# Nixius.net
KiCad netlist of a schematic drawn in EAGLE
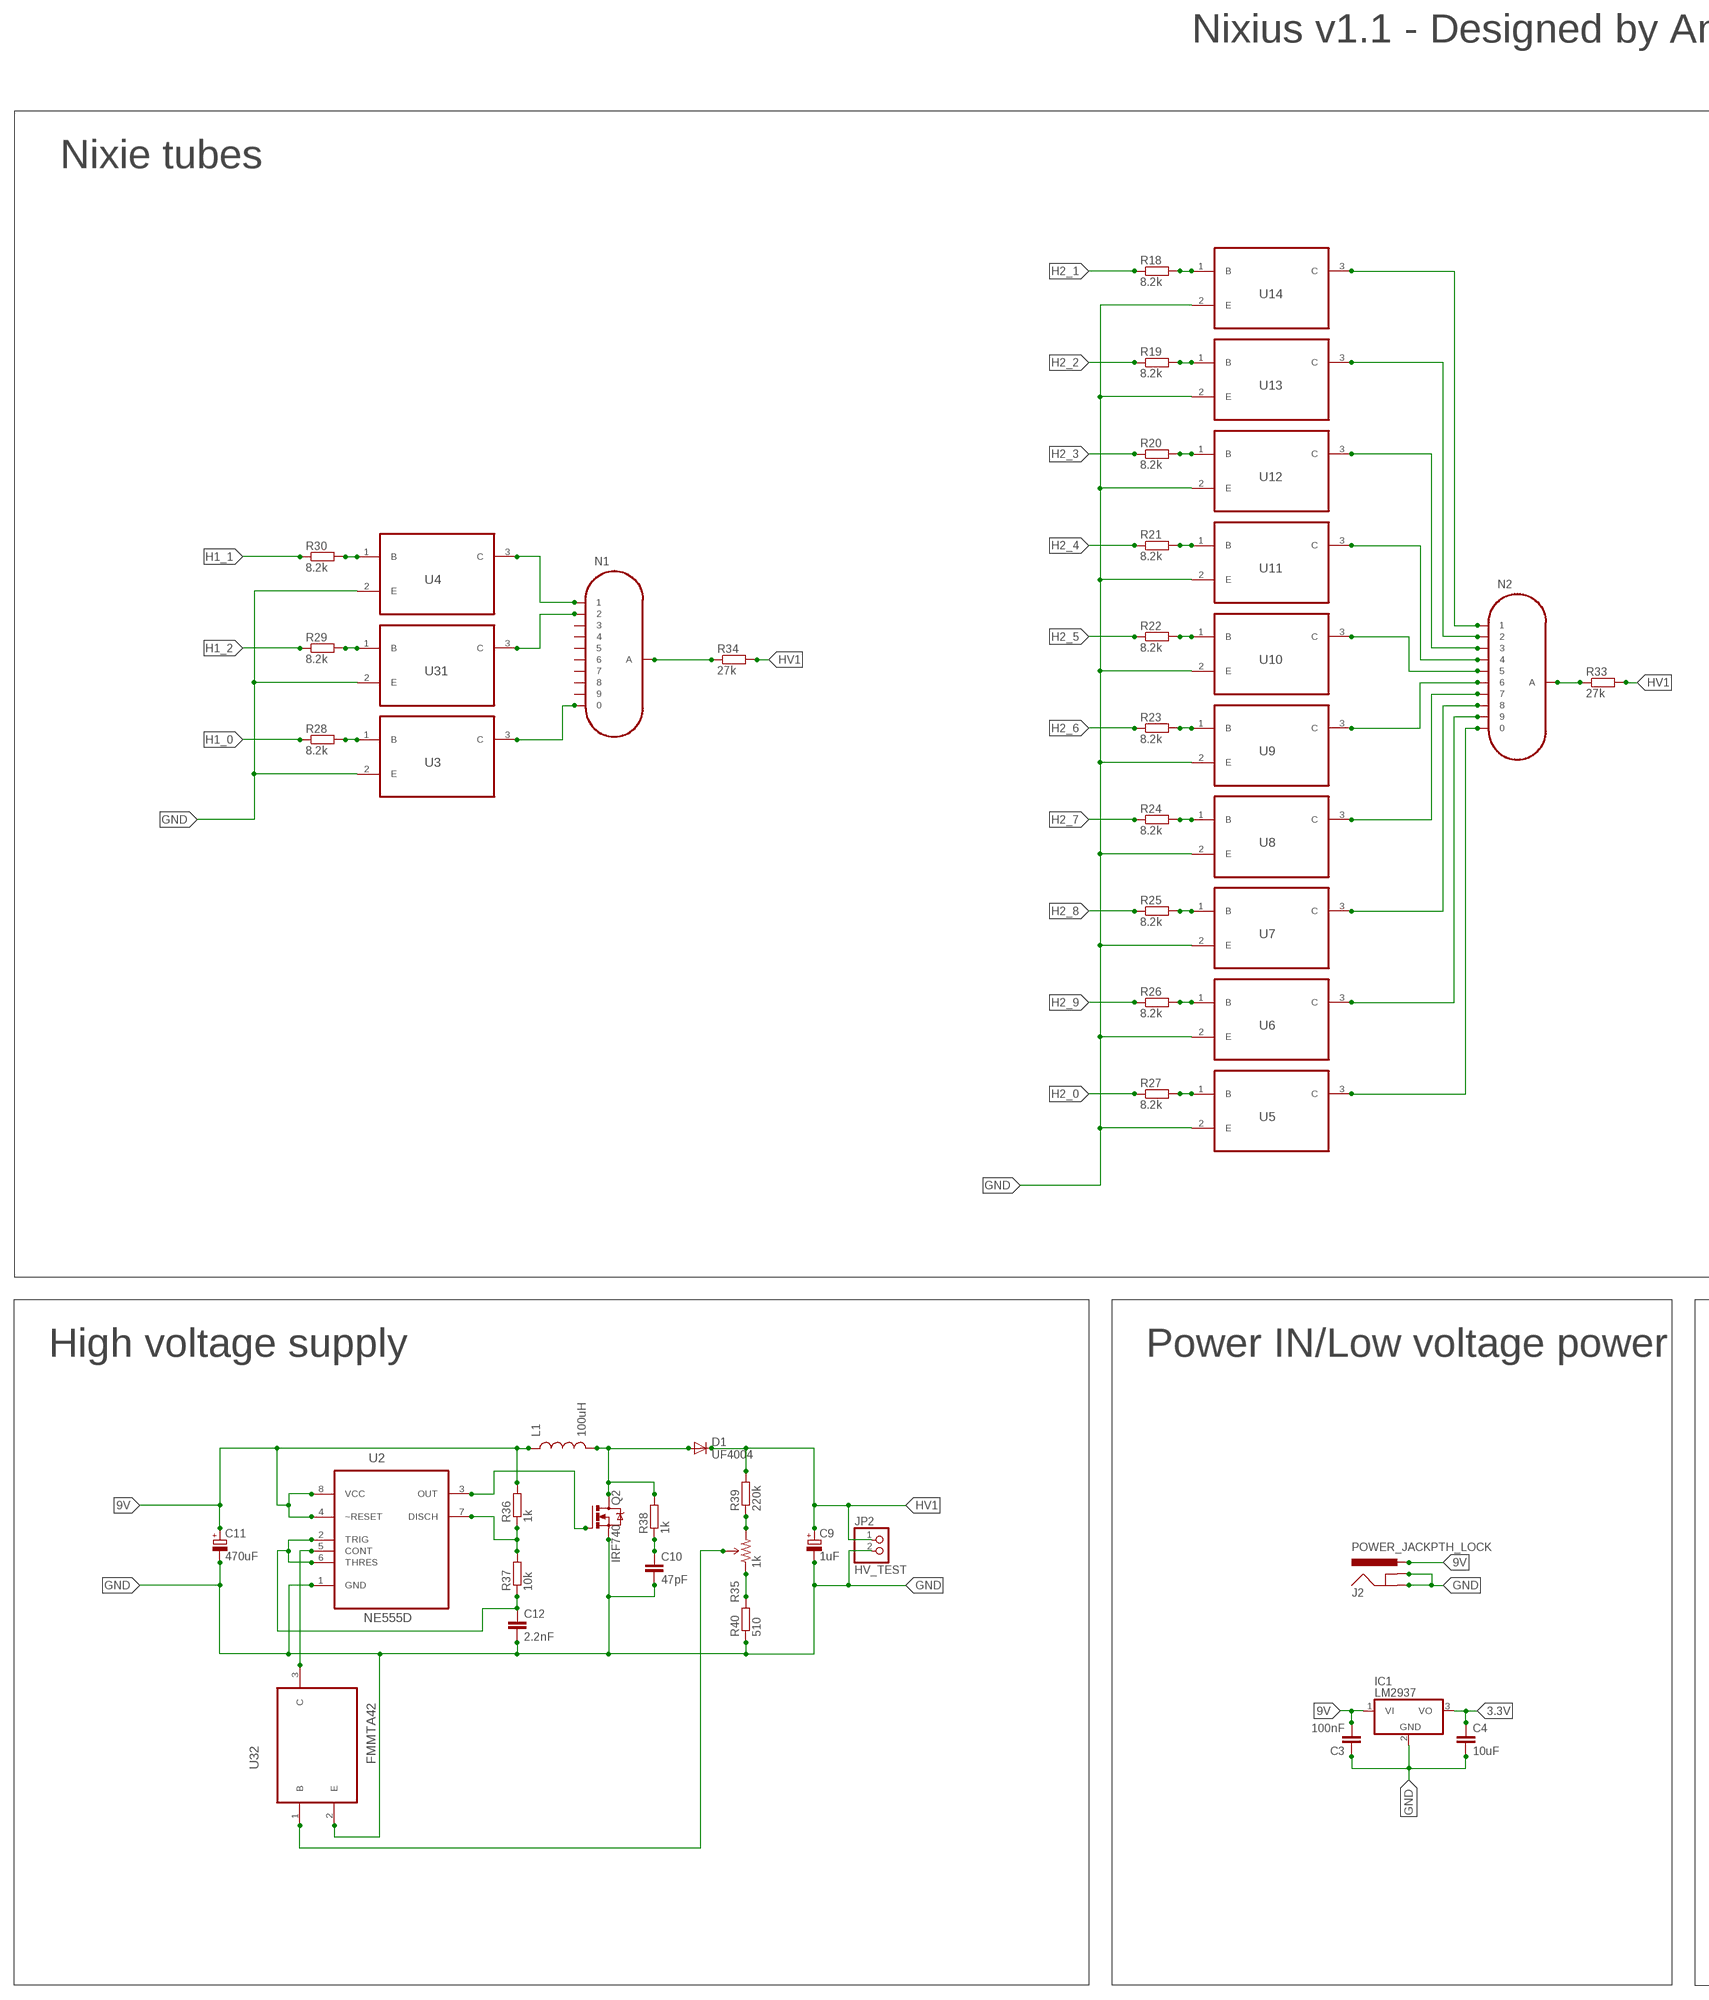
[diagram p0: schematic, sheet 1, part 1 of 2]
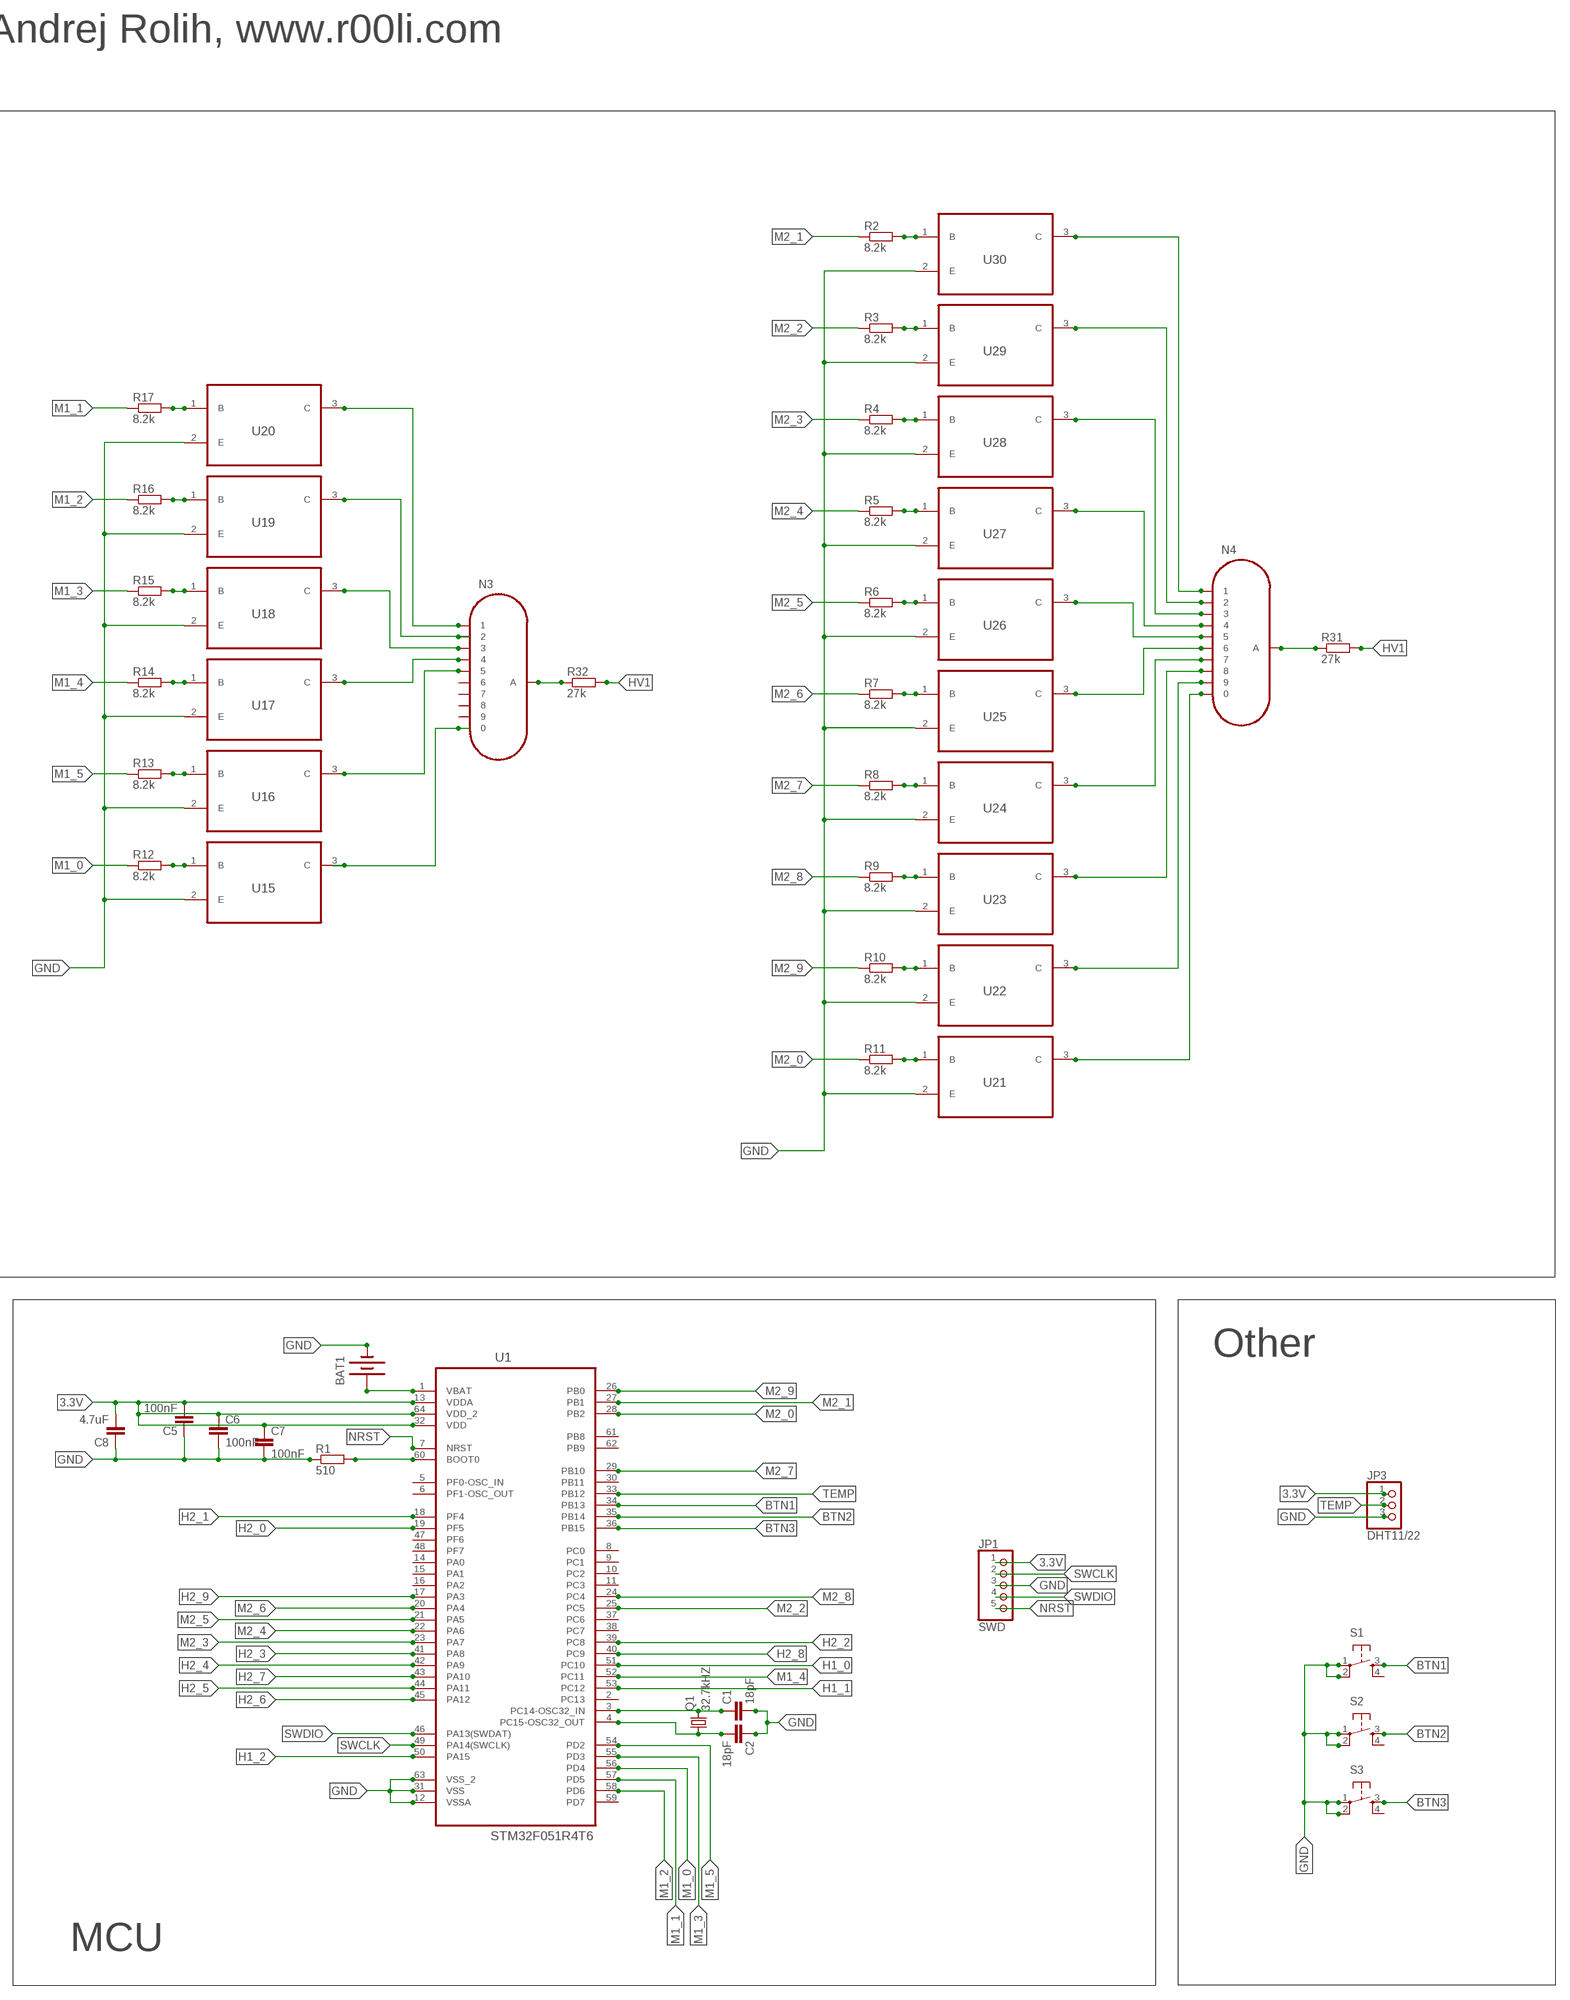
[diagram p1: schematic, sheet 1, part 2 of 2]

(export (version "E")
  (design (tool "Eeschema 10.0.6"))
  (components
    (comp (ref "BAT1")
      (value "BATTERY20SMD")
      (footprint "eagle-import:BATTCON_20MM")
      (libsource (lib "eagle-import") (part "BATTERY20SMD"))
    )
    (comp (ref "C1")
      (value "18pF")
      (footprint "eagle-import:0805")
      (libsource (lib "eagle-import") (part "CAP0805"))
    )
    (comp (ref "C2")
      (value "18pF")
      (footprint "eagle-import:0805")
      (libsource (lib "eagle-import") (part "CAP0805"))
    )
    (comp (ref "C3")
      (value "100nF")
      (footprint "eagle-import:0805")
      (libsource (lib "eagle-import") (part "CAP0805"))
    )
    (comp (ref "C4")
      (value "10uF")
      (footprint "eagle-import:0805")
      (libsource (lib "eagle-import") (part "CAP0805"))
    )
    (comp (ref "C5")
      (value "100nF")
      (footprint "eagle-import:0805")
      (libsource (lib "eagle-import") (part "CAP0805"))
    )
    (comp (ref "C6")
      (value "100nF")
      (footprint "eagle-import:0805")
      (libsource (lib "eagle-import") (part "CAP0805"))
    )
    (comp (ref "C7")
      (value "100nF")
      (footprint "eagle-import:0805")
      (libsource (lib "eagle-import") (part "CAP0805"))
    )
    (comp (ref "C8")
      (value "4.7uF")
      (footprint "eagle-import:0805")
      (libsource (lib "eagle-import") (part "CAP0805"))
    )
    (comp (ref "C9")
      (value "1uF")
      (footprint "eagle-import:E2,5-6")
      (libsource (lib "eagle-import") (part "CPOL-EUE2.5-6"))
    )
    (comp (ref "C10")
      (value "47pF")
      (footprint "eagle-import:0805")
      (libsource (lib "eagle-import") (part "CAP0805"))
    )
    (comp (ref "C11")
      (value "470uF")
      (footprint "eagle-import:E3,5-8")
      (libsource (lib "eagle-import") (part "CPOL-EUE3.5-8"))
    )
    (comp (ref "C12")
      (value "2.2nF")
      (footprint "eagle-import:C050-025X075")
      (libsource (lib "eagle-import") (part "C-EU050-025X075"))
    )
    (comp (ref "D1")
      (value "UF4004")
      (footprint "eagle-import:DO41-10")
      (libsource (lib "eagle-import") (part "1N4004"))
    )
    (comp (ref "IC1")
      (value "LM2937")
      (footprint "eagle-import:TO263-3")
      (libsource (lib "eagle-import") (part "LM2937"))
    )
    (comp (ref "J2")
      (value "POWER_JACKPTH_LOCK")
      (footprint "eagle-import:POWER_JACK_PTH_LOCK")
      (libsource (lib "eagle-import") (part "POWER_JACKPTH_LOCK"))
    )
    (comp (ref "JP1")
      (value "SWD")
      (footprint "eagle-import:1X05")
      (libsource (lib "eagle-import") (part "PINHD-1X5"))
    )
    (comp (ref "JP2")
      (value "HV_TEST")
      (footprint "eagle-import:1X02")
      (libsource (lib "eagle-import") (part "PINHD-1X2"))
    )
    (comp (ref "JP3")
      (value "DHT11/22")
      (footprint "eagle-import:1X03")
      (libsource (lib "eagle-import") (part "PINHD-1X3"))
    )
    (comp (ref "L1")
      (value "100uH")
      (footprint "eagle-import:RLB0912")
      (libsource (lib "eagle-import") (part "INDUCTORRLB0912"))
    )
    (comp (ref "N1")
      (value "IN-1")
      (footprint "eagle-import:IN-1")
      (libsource (lib "eagle-import") (part "IN-1"))
    )
    (comp (ref "N2")
      (value "IN-1")
      (footprint "eagle-import:IN-1")
      (libsource (lib "eagle-import") (part "IN-1"))
    )
    (comp (ref "N3")
      (value "IN-1")
      (footprint "eagle-import:IN-1")
      (libsource (lib "eagle-import") (part "IN-1"))
    )
    (comp (ref "N4")
      (value "IN-1")
      (footprint "eagle-import:IN-1")
      (libsource (lib "eagle-import") (part "IN-1"))
    )
    (comp (ref "Q1")
      (value "32.7kHZ")
      (footprint "eagle-import:MC-306")
      (fields (field (name "MPN") "MC-306 60.0KHZ  100PPM ,12.5PF"))
      (libsource (lib "eagle-import") (part "MC-306"))
    )
    (comp (ref "Q2")
      (value "IRF740")
      (footprint "eagle-import:TO220BV")
      (libsource (lib "eagle-import") (part "IRF740"))
    )
    (comp (ref "R1")
      (value "510")
      (footprint "eagle-import:R0805")
      (libsource (lib "eagle-import") (part "resistor_R-EU_R0805"))
    )
    (comp (ref "R2")
      (value "8.2k")
      (footprint "eagle-import:R0805")
      (libsource (lib "eagle-import") (part "resistor_R-EU_R0805"))
    )
    (comp (ref "R3")
      (value "8.2k")
      (footprint "eagle-import:R0805")
      (libsource (lib "eagle-import") (part "resistor_R-EU_R0805"))
    )
    (comp (ref "R4")
      (value "8.2k")
      (footprint "eagle-import:R0805")
      (libsource (lib "eagle-import") (part "resistor_R-EU_R0805"))
    )
    (comp (ref "R5")
      (value "8.2k")
      (footprint "eagle-import:R0805")
      (libsource (lib "eagle-import") (part "resistor_R-EU_R0805"))
    )
    (comp (ref "R6")
      (value "8.2k")
      (footprint "eagle-import:R0805")
      (libsource (lib "eagle-import") (part "resistor_R-EU_R0805"))
    )
    (comp (ref "R7")
      (value "8.2k")
      (footprint "eagle-import:R0805")
      (libsource (lib "eagle-import") (part "resistor_R-EU_R0805"))
    )
    (comp (ref "R8")
      (value "8.2k")
      (footprint "eagle-import:R0805")
      (libsource (lib "eagle-import") (part "resistor_R-EU_R0805"))
    )
    (comp (ref "R9")
      (value "8.2k")
      (footprint "eagle-import:R0805")
      (libsource (lib "eagle-import") (part "resistor_R-EU_R0805"))
    )
    (comp (ref "R10")
      (value "8.2k")
      (footprint "eagle-import:R0805")
      (libsource (lib "eagle-import") (part "resistor_R-EU_R0805"))
    )
    (comp (ref "R11")
      (value "8.2k")
      (footprint "eagle-import:R0805")
      (libsource (lib "eagle-import") (part "resistor_R-EU_R0805"))
    )
    (comp (ref "R12")
      (value "8.2k")
      (footprint "eagle-import:R0805")
      (libsource (lib "eagle-import") (part "resistor_R-EU_R0805"))
    )
    (comp (ref "R13")
      (value "8.2k")
      (footprint "eagle-import:R0805")
      (libsource (lib "eagle-import") (part "resistor_R-EU_R0805"))
    )
    (comp (ref "R14")
      (value "8.2k")
      (footprint "eagle-import:R0805")
      (libsource (lib "eagle-import") (part "resistor_R-EU_R0805"))
    )
    (comp (ref "R15")
      (value "8.2k")
      (footprint "eagle-import:R0805")
      (libsource (lib "eagle-import") (part "resistor_R-EU_R0805"))
    )
    (comp (ref "R16")
      (value "8.2k")
      (footprint "eagle-import:R0805")
      (libsource (lib "eagle-import") (part "resistor_R-EU_R0805"))
    )
    (comp (ref "R17")
      (value "8.2k")
      (footprint "eagle-import:R0805")
      (libsource (lib "eagle-import") (part "resistor_R-EU_R0805"))
    )
    (comp (ref "R18")
      (value "8.2k")
      (footprint "eagle-import:R0805")
      (libsource (lib "eagle-import") (part "resistor_R-EU_R0805"))
    )
    (comp (ref "R19")
      (value "8.2k")
      (footprint "eagle-import:R0805")
      (libsource (lib "eagle-import") (part "resistor_R-EU_R0805"))
    )
    (comp (ref "R20")
      (value "8.2k")
      (footprint "eagle-import:R0805")
      (libsource (lib "eagle-import") (part "resistor_R-EU_R0805"))
    )
    (comp (ref "R21")
      (value "8.2k")
      (footprint "eagle-import:R0805")
      (libsource (lib "eagle-import") (part "resistor_R-EU_R0805"))
    )
    (comp (ref "R22")
      (value "8.2k")
      (footprint "eagle-import:R0805")
      (libsource (lib "eagle-import") (part "resistor_R-EU_R0805"))
    )
    (comp (ref "R23")
      (value "8.2k")
      (footprint "eagle-import:R0805")
      (libsource (lib "eagle-import") (part "resistor_R-EU_R0805"))
    )
    (comp (ref "R24")
      (value "8.2k")
      (footprint "eagle-import:R0805")
      (libsource (lib "eagle-import") (part "resistor_R-EU_R0805"))
    )
    (comp (ref "R25")
      (value "8.2k")
      (footprint "eagle-import:R0805")
      (libsource (lib "eagle-import") (part "resistor_R-EU_R0805"))
    )
    (comp (ref "R26")
      (value "8.2k")
      (footprint "eagle-import:R0805")
      (libsource (lib "eagle-import") (part "resistor_R-EU_R0805"))
    )
    (comp (ref "R27")
      (value "8.2k")
      (footprint "eagle-import:R0805")
      (libsource (lib "eagle-import") (part "resistor_R-EU_R0805"))
    )
    (comp (ref "R28")
      (value "8.2k")
      (footprint "eagle-import:R0805")
      (libsource (lib "eagle-import") (part "resistor_R-EU_R0805"))
    )
    (comp (ref "R29")
      (value "8.2k")
      (footprint "eagle-import:R0805")
      (libsource (lib "eagle-import") (part "resistor_R-EU_R0805"))
    )
    (comp (ref "R30")
      (value "8.2k")
      (footprint "eagle-import:R0805")
      (libsource (lib "eagle-import") (part "resistor_R-EU_R0805"))
    )
    (comp (ref "R31")
      (value "27k")
      (footprint "eagle-import:R1206")
      (libsource (lib "eagle-import") (part "resistor_R-EU_R1206"))
    )
    (comp (ref "R32")
      (value "27k")
      (footprint "eagle-import:R1206")
      (libsource (lib "eagle-import") (part "resistor_R-EU_R1206"))
    )
    (comp (ref "R33")
      (value "27k")
      (footprint "eagle-import:R1206")
      (libsource (lib "eagle-import") (part "resistor_R-EU_R1206"))
    )
    (comp (ref "R34")
      (value "27k")
      (footprint "eagle-import:R1206")
      (libsource (lib "eagle-import") (part "resistor_R-EU_R1206"))
    )
    (comp (ref "R35")
      (value "1k")
      (footprint "eagle-import:3362U-2")
      (libsource (lib "eagle-import") (part "TRIMPOT3362U-2"))
    )
    (comp (ref "R36")
      (value "1k")
      (footprint "eagle-import:R0805")
      (libsource (lib "eagle-import") (part "resistor_R-EU_R0805"))
    )
    (comp (ref "R37")
      (value "10k")
      (footprint "eagle-import:R0805")
      (libsource (lib "eagle-import") (part "resistor_R-EU_R0805"))
    )
    (comp (ref "R38")
      (value "1k")
      (footprint "eagle-import:R0805")
      (libsource (lib "eagle-import") (part "resistor_R-EU_R0805"))
    )
    (comp (ref "R39")
      (value "220k")
      (footprint "eagle-import:R1206")
      (libsource (lib "eagle-import") (part "R-EU_R1206"))
    )
    (comp (ref "R40")
      (value "510")
      (footprint "eagle-import:R0805")
      (libsource (lib "eagle-import") (part "resistor_R-EU_R0805"))
    )
    (comp (ref "S1")
      (value "TAC_SWITCHPTH")
      (footprint "eagle-import:TACTILE-PTH")
      (libsource (lib "eagle-import") (part "TAC_SWITCHPTH"))
    )
    (comp (ref "S2")
      (value "TAC_SWITCHPTH")
      (footprint "eagle-import:TACTILE-PTH")
      (libsource (lib "eagle-import") (part "TAC_SWITCHPTH"))
    )
    (comp (ref "S3")
      (value "TAC_SWITCHPTH")
      (footprint "eagle-import:TACTILE-PTH")
      (libsource (lib "eagle-import") (part "TAC_SWITCHPTH"))
    )
    (comp (ref "U1")
      (value "STM32F051R4T6")
      (footprint "eagle-import:QFP50P1200X1200X160-64N")
      (libsource (lib "eagle-import") (part "STM32F051R4T6"))
    )
    (comp (ref "U2")
      (value "NE555D")
      (footprint "eagle-import:SOIC127P600X175-8N")
      (libsource (lib "eagle-import") (part "NE555D"))
    )
    (comp (ref "U3")
      (value "FMMTA42")
      (footprint "eagle-import:SOT95P240X110-3N")
      (libsource (lib "eagle-import") (part "FMMTA42"))
    )
    (comp (ref "U4")
      (value "FMMTA42")
      (footprint "eagle-import:SOT95P240X110-3N")
      (libsource (lib "eagle-import") (part "FMMTA42"))
    )
    (comp (ref "U5")
      (value "FMMTA42")
      (footprint "eagle-import:SOT95P240X110-3N")
      (libsource (lib "eagle-import") (part "FMMTA42"))
    )
    (comp (ref "U6")
      (value "FMMTA42")
      (footprint "eagle-import:SOT95P240X110-3N")
      (libsource (lib "eagle-import") (part "FMMTA42"))
    )
    (comp (ref "U7")
      (value "FMMTA42")
      (footprint "eagle-import:SOT95P240X110-3N")
      (libsource (lib "eagle-import") (part "FMMTA42"))
    )
    (comp (ref "U8")
      (value "FMMTA42")
      (footprint "eagle-import:SOT95P240X110-3N")
      (libsource (lib "eagle-import") (part "FMMTA42"))
    )
    (comp (ref "U9")
      (value "FMMTA42")
      (footprint "eagle-import:SOT95P240X110-3N")
      (libsource (lib "eagle-import") (part "FMMTA42"))
    )
    (comp (ref "U10")
      (value "FMMTA42")
      (footprint "eagle-import:SOT95P240X110-3N")
      (libsource (lib "eagle-import") (part "FMMTA42"))
    )
    (comp (ref "U11")
      (value "FMMTA42")
      (footprint "eagle-import:SOT95P240X110-3N")
      (libsource (lib "eagle-import") (part "FMMTA42"))
    )
    (comp (ref "U12")
      (value "FMMTA42")
      (footprint "eagle-import:SOT95P240X110-3N")
      (libsource (lib "eagle-import") (part "FMMTA42"))
    )
    (comp (ref "U13")
      (value "FMMTA42")
      (footprint "eagle-import:SOT95P240X110-3N")
      (libsource (lib "eagle-import") (part "FMMTA42"))
    )
    (comp (ref "U14")
      (value "FMMTA42")
      (footprint "eagle-import:SOT95P240X110-3N")
      (libsource (lib "eagle-import") (part "FMMTA42"))
    )
    (comp (ref "U15")
      (value "FMMTA42")
      (footprint "eagle-import:SOT95P240X110-3N")
      (libsource (lib "eagle-import") (part "FMMTA42"))
    )
    (comp (ref "U16")
      (value "FMMTA42")
      (footprint "eagle-import:SOT95P240X110-3N")
      (libsource (lib "eagle-import") (part "FMMTA42"))
    )
    (comp (ref "U17")
      (value "FMMTA42")
      (footprint "eagle-import:SOT95P240X110-3N")
      (libsource (lib "eagle-import") (part "FMMTA42"))
    )
    (comp (ref "U18")
      (value "FMMTA42")
      (footprint "eagle-import:SOT95P240X110-3N")
      (libsource (lib "eagle-import") (part "FMMTA42"))
    )
    (comp (ref "U19")
      (value "FMMTA42")
      (footprint "eagle-import:SOT95P240X110-3N")
      (libsource (lib "eagle-import") (part "FMMTA42"))
    )
    (comp (ref "U20")
      (value "FMMTA42")
      (footprint "eagle-import:SOT95P240X110-3N")
      (libsource (lib "eagle-import") (part "FMMTA42"))
    )
    (comp (ref "U21")
      (value "FMMTA42")
      (footprint "eagle-import:SOT95P240X110-3N")
      (libsource (lib "eagle-import") (part "FMMTA42"))
    )
    (comp (ref "U22")
      (value "FMMTA42")
      (footprint "eagle-import:SOT95P240X110-3N")
      (libsource (lib "eagle-import") (part "FMMTA42"))
    )
    (comp (ref "U23")
      (value "FMMTA42")
      (footprint "eagle-import:SOT95P240X110-3N")
      (libsource (lib "eagle-import") (part "FMMTA42"))
    )
    (comp (ref "U24")
      (value "FMMTA42")
      (footprint "eagle-import:SOT95P240X110-3N")
      (libsource (lib "eagle-import") (part "FMMTA42"))
    )
    (comp (ref "U25")
      (value "FMMTA42")
      (footprint "eagle-import:SOT95P240X110-3N")
      (libsource (lib "eagle-import") (part "FMMTA42"))
    )
    (comp (ref "U26")
      (value "FMMTA42")
      (footprint "eagle-import:SOT95P240X110-3N")
      (libsource (lib "eagle-import") (part "FMMTA42"))
    )
    (comp (ref "U27")
      (value "FMMTA42")
      (footprint "eagle-import:SOT95P240X110-3N")
      (libsource (lib "eagle-import") (part "FMMTA42"))
    )
    (comp (ref "U28")
      (value "FMMTA42")
      (footprint "eagle-import:SOT95P240X110-3N")
      (libsource (lib "eagle-import") (part "FMMTA42"))
    )
    (comp (ref "U29")
      (value "FMMTA42")
      (footprint "eagle-import:SOT95P240X110-3N")
      (libsource (lib "eagle-import") (part "FMMTA42"))
    )
    (comp (ref "U30")
      (value "FMMTA42")
      (footprint "eagle-import:SOT95P240X110-3N")
      (libsource (lib "eagle-import") (part "FMMTA42"))
    )
    (comp (ref "U31")
      (value "FMMTA42")
      (footprint "eagle-import:SOT95P240X110-3N")
      (libsource (lib "eagle-import") (part "FMMTA42"))
    )
    (comp (ref "U32")
      (value "FMMTA42")
      (footprint "eagle-import:SOT95P240X110-3N")
      (libsource (lib "eagle-import") (part "FMMTA42"))
    )
  )
  (nets
    (net (code "1") (name "3.3V") (class "Default")
      (node (ref "C4") (pin "1") (pinfunction "1_1") (pintype "passive"))
      (node (ref "C5") (pin "2") (pinfunction "2_2") (pintype "passive"))
      (node (ref "C6") (pin "1") (pinfunction "1_1") (pintype "passive"))
      (node (ref "C7") (pin "1") (pinfunction "1_1") (pintype "passive"))
      (node (ref "C8") (pin "2") (pinfunction "2_2") (pintype "passive"))
      (node (ref "IC1") (pin "3") (pinfunction "VO_3") (pintype "passive"))
      (node (ref "JP1") (pin "1") (pinfunction "1_1") (pintype "passive"))
      (node (ref "JP3") (pin "1") (pinfunction "1_1") (pintype "passive"))
      (node (ref "U1") (pin "13") (pinfunction "VDDA_13") (pintype "power_in"))
      (node (ref "U1") (pin "32") (pinfunction "VDD_32") (pintype "power_in"))
      (node (ref "U1") (pin "64") (pinfunction "VDD_2_64") (pintype "power_in"))
    )
    (net (code "2") (name "9V") (class "Default")
      (node (ref "C11") (pin "+") (pinfunction "+_+") (pintype "passive"))
      (node (ref "C3") (pin "2") (pinfunction "2_2") (pintype "passive"))
      (node (ref "IC1") (pin "1") (pinfunction "VI_1") (pintype "input"))
      (node (ref "J2") (pin "PWR") (pinfunction "PWR_PWR") (pintype "bidirectional"))
      (node (ref "L1") (pin "1") (pinfunction "1_1") (pintype "passive"))
      (node (ref "R36") (pin "2") (pinfunction "2_2") (pintype "passive"))
      (node (ref "U2") (pin "4") (pinfunction "~{RESET}_4") (pintype "input"))
      (node (ref "U2") (pin "8") (pinfunction "VCC_8") (pintype "power_in"))
    )
    (net (code "3") (name "BTN1") (class "Default")
      (node (ref "S1") (pin "3") (pinfunction "3_3") (pintype "passive"))
      (node (ref "U1") (pin "34") (pinfunction "PB13_34") (pintype "bidirectional"))
    )
    (net (code "4") (name "BTN2") (class "Default")
      (node (ref "S2") (pin "3") (pinfunction "3_3") (pintype "passive"))
      (node (ref "U1") (pin "35") (pinfunction "PB14_35") (pintype "bidirectional"))
    )
    (net (code "5") (name "BTN3") (class "Default")
      (node (ref "S3") (pin "3") (pinfunction "3_3") (pintype "passive"))
      (node (ref "U1") (pin "36") (pinfunction "PB15_36") (pintype "bidirectional"))
    )
    (net (code "6") (name "GND") (class "Default")
      (node (ref "BAT1") (pin "2") (pinfunction "-_2") (pintype "power_in"))
      (node (ref "C1") (pin "2") (pinfunction "2_2") (pintype "passive"))
      (node (ref "C10") (pin "2") (pinfunction "2_2") (pintype "passive"))
      (node (ref "C11") (pin "-") (pinfunction "-_-") (pintype "passive"))
      (node (ref "C12") (pin "2") (pinfunction "2_2") (pintype "passive"))
      (node (ref "C2") (pin "1") (pinfunction "1_1") (pintype "passive"))
      (node (ref "C3") (pin "1") (pinfunction "1_1") (pintype "passive"))
      (node (ref "C4") (pin "2") (pinfunction "2_2") (pintype "passive"))
      (node (ref "C5") (pin "1") (pinfunction "1_1") (pintype "passive"))
      (node (ref "C6") (pin "2") (pinfunction "2_2") (pintype "passive"))
      (node (ref "C7") (pin "2") (pinfunction "2_2") (pintype "passive"))
      (node (ref "C8") (pin "1") (pinfunction "1_1") (pintype "passive"))
      (node (ref "C9") (pin "-") (pinfunction "-_-") (pintype "passive"))
      (node (ref "IC1") (pin "2") (pinfunction "GND_2") (pintype "passive"))
      (node (ref "J2") (pin "GND") (pinfunction "GND_GND") (pintype "bidirectional"))
      (node (ref "J2") (pin "GNDBREAK") (pinfunction "GNDBREAK_GNDBREAK") (pintype "bidirectional"))
      (node (ref "JP1") (pin "3") (pinfunction "3_3") (pintype "passive"))
      (node (ref "JP2") (pin "2") (pinfunction "2_2") (pintype "passive"))
      (node (ref "JP3") (pin "3") (pinfunction "3_3") (pintype "passive"))
      (node (ref "Q2") (pin "S") (pinfunction "S_S") (pintype "passive"))
      (node (ref "R1") (pin "1") (pinfunction "1_1") (pintype "passive"))
      (node (ref "R40") (pin "1") (pinfunction "1_1") (pintype "passive"))
      (node (ref "S1") (pin "1") (pinfunction "1_1") (pintype "passive"))
      (node (ref "S1") (pin "2") (pinfunction "2_2") (pintype "passive"))
      (node (ref "S2") (pin "1") (pinfunction "1_1") (pintype "passive"))
      (node (ref "S2") (pin "2") (pinfunction "2_2") (pintype "passive"))
      (node (ref "S3") (pin "1") (pinfunction "1_1") (pintype "passive"))
      (node (ref "S3") (pin "2") (pinfunction "2_2") (pintype "passive"))
      (node (ref "U1") (pin "12") (pinfunction "VSSA_12") (pintype "passive"))
      (node (ref "U1") (pin "31") (pinfunction "VSS_31") (pintype "passive"))
      (node (ref "U1") (pin "63") (pinfunction "VSS_2_63") (pintype "passive"))
      (node (ref "U10") (pin "2") (pinfunction "E_2") (pintype "passive"))
      (node (ref "U11") (pin "2") (pinfunction "E_2") (pintype "passive"))
      (node (ref "U12") (pin "2") (pinfunction "E_2") (pintype "passive"))
      (node (ref "U13") (pin "2") (pinfunction "E_2") (pintype "passive"))
      (node (ref "U14") (pin "2") (pinfunction "E_2") (pintype "passive"))
      (node (ref "U15") (pin "2") (pinfunction "E_2") (pintype "passive"))
      (node (ref "U16") (pin "2") (pinfunction "E_2") (pintype "passive"))
      (node (ref "U17") (pin "2") (pinfunction "E_2") (pintype "passive"))
      (node (ref "U18") (pin "2") (pinfunction "E_2") (pintype "passive"))
      (node (ref "U19") (pin "2") (pinfunction "E_2") (pintype "passive"))
      (node (ref "U2") (pin "1") (pinfunction "GND_1") (pintype "passive"))
      (node (ref "U20") (pin "2") (pinfunction "E_2") (pintype "passive"))
      (node (ref "U21") (pin "2") (pinfunction "E_2") (pintype "passive"))
      (node (ref "U22") (pin "2") (pinfunction "E_2") (pintype "passive"))
      (node (ref "U23") (pin "2") (pinfunction "E_2") (pintype "passive"))
      (node (ref "U24") (pin "2") (pinfunction "E_2") (pintype "passive"))
      (node (ref "U25") (pin "2") (pinfunction "E_2") (pintype "passive"))
      (node (ref "U26") (pin "2") (pinfunction "E_2") (pintype "passive"))
      (node (ref "U27") (pin "2") (pinfunction "E_2") (pintype "passive"))
      (node (ref "U28") (pin "2") (pinfunction "E_2") (pintype "passive"))
      (node (ref "U29") (pin "2") (pinfunction "E_2") (pintype "passive"))
      (node (ref "U3") (pin "2") (pinfunction "E_2") (pintype "passive"))
      (node (ref "U30") (pin "2") (pinfunction "E_2") (pintype "passive"))
      (node (ref "U31") (pin "2") (pinfunction "E_2") (pintype "passive"))
      (node (ref "U32") (pin "2") (pinfunction "E_2") (pintype "passive"))
      (node (ref "U4") (pin "2") (pinfunction "E_2") (pintype "passive"))
      (node (ref "U5") (pin "2") (pinfunction "E_2") (pintype "passive"))
      (node (ref "U6") (pin "2") (pinfunction "E_2") (pintype "passive"))
      (node (ref "U7") (pin "2") (pinfunction "E_2") (pintype "passive"))
      (node (ref "U8") (pin "2") (pinfunction "E_2") (pintype "passive"))
      (node (ref "U9") (pin "2") (pinfunction "E_2") (pintype "passive"))
    )
    (net (code "7") (name "H1_0") (class "Default")
      (node (ref "R28") (pin "1") (pinfunction "1_1") (pintype "passive"))
      (node (ref "U1") (pin "51") (pinfunction "PC10_51") (pintype "bidirectional"))
    )
    (net (code "8") (name "H1_1") (class "Default")
      (node (ref "R30") (pin "1") (pinfunction "1_1") (pintype "passive"))
      (node (ref "U1") (pin "53") (pinfunction "PC12_53") (pintype "bidirectional"))
    )
    (net (code "9") (name "H1_2") (class "Default")
      (node (ref "R29") (pin "1") (pinfunction "1_1") (pintype "passive"))
      (node (ref "U1") (pin "50") (pinfunction "PA15_50") (pintype "bidirectional"))
    )
    (net (code "10") (name "H2_0") (class "Default")
      (node (ref "R27") (pin "1") (pinfunction "1_1") (pintype "passive"))
      (node (ref "U1") (pin "19") (pinfunction "PF5_19") (pintype "bidirectional"))
    )
    (net (code "11") (name "H2_1") (class "Default")
      (node (ref "R18") (pin "1") (pinfunction "1_1") (pintype "passive"))
      (node (ref "U1") (pin "18") (pinfunction "PF4_18") (pintype "bidirectional"))
    )
    (net (code "12") (name "H2_2") (class "Default")
      (node (ref "R19") (pin "1") (pinfunction "1_1") (pintype "passive"))
      (node (ref "U1") (pin "39") (pinfunction "PC8_39") (pintype "bidirectional"))
    )
    (net (code "13") (name "H2_3") (class "Default")
      (node (ref "R20") (pin "1") (pinfunction "1_1") (pintype "passive"))
      (node (ref "U1") (pin "41") (pinfunction "PA8_41") (pintype "bidirectional"))
    )
    (net (code "14") (name "H2_4") (class "Default")
      (node (ref "R21") (pin "1") (pinfunction "1_1") (pintype "passive"))
      (node (ref "U1") (pin "42") (pinfunction "PA9_42") (pintype "bidirectional"))
    )
    (net (code "15") (name "H2_5") (class "Default")
      (node (ref "R22") (pin "1") (pinfunction "1_1") (pintype "passive"))
      (node (ref "U1") (pin "44") (pinfunction "PA11_44") (pintype "bidirectional"))
    )
    (net (code "16") (name "H2_6") (class "Default")
      (node (ref "R23") (pin "1") (pinfunction "1_1") (pintype "passive"))
      (node (ref "U1") (pin "45") (pinfunction "PA12_45") (pintype "bidirectional"))
    )
    (net (code "17") (name "H2_7") (class "Default")
      (node (ref "R24") (pin "1") (pinfunction "1_1") (pintype "passive"))
      (node (ref "U1") (pin "43") (pinfunction "PA10_43") (pintype "bidirectional"))
    )
    (net (code "18") (name "H2_8") (class "Default")
      (node (ref "R25") (pin "1") (pinfunction "1_1") (pintype "passive"))
      (node (ref "U1") (pin "40") (pinfunction "PC9_40") (pintype "bidirectional"))
    )
    (net (code "19") (name "H2_9") (class "Default")
      (node (ref "R26") (pin "1") (pinfunction "1_1") (pintype "passive"))
      (node (ref "U1") (pin "17") (pinfunction "PA3_17") (pintype "bidirectional"))
    )
    (net (code "20") (name "HV1") (class "Default")
      (node (ref "C9") (pin "+") (pinfunction "+_+") (pintype "passive"))
      (node (ref "D1") (pin "C") (pinfunction "C_C") (pintype "passive"))
      (node (ref "JP2") (pin "1") (pinfunction "1_1") (pintype "passive"))
      (node (ref "R31") (pin "2") (pinfunction "2_2") (pintype "passive"))
      (node (ref "R32") (pin "2") (pinfunction "2_2") (pintype "passive"))
      (node (ref "R33") (pin "2") (pinfunction "2_2") (pintype "passive"))
      (node (ref "R34") (pin "2") (pinfunction "2_2") (pintype "passive"))
      (node (ref "R39") (pin "2") (pinfunction "2_2") (pintype "passive"))
    )
    (net (code "21") (name "M1_0") (class "Default")
      (node (ref "R12") (pin "1") (pinfunction "1_1") (pintype "passive"))
      (node (ref "U1") (pin "56") (pinfunction "PD4_56") (pintype "bidirectional"))
    )
    (net (code "22") (name "M1_1") (class "Default")
      (node (ref "R17") (pin "1") (pinfunction "1_1") (pintype "passive"))
      (node (ref "U1") (pin "57") (pinfunction "PD5_57") (pintype "bidirectional"))
    )
    (net (code "23") (name "M1_2") (class "Default")
      (node (ref "R16") (pin "1") (pinfunction "1_1") (pintype "passive"))
      (node (ref "U1") (pin "58") (pinfunction "PD6_58") (pintype "bidirectional"))
    )
    (net (code "24") (name "M1_3") (class "Default")
      (node (ref "R15") (pin "1") (pinfunction "1_1") (pintype "passive"))
      (node (ref "U1") (pin "55") (pinfunction "PD3_55") (pintype "bidirectional"))
    )
    (net (code "25") (name "M1_4") (class "Default")
      (node (ref "R14") (pin "1") (pinfunction "1_1") (pintype "passive"))
      (node (ref "U1") (pin "52") (pinfunction "PC11_52") (pintype "bidirectional"))
    )
    (net (code "26") (name "M1_5") (class "Default")
      (node (ref "R13") (pin "1") (pinfunction "1_1") (pintype "passive"))
      (node (ref "U1") (pin "54") (pinfunction "PD2_54") (pintype "bidirectional"))
    )
    (net (code "27") (name "M2_0") (class "Default")
      (node (ref "R11") (pin "1") (pinfunction "1_1") (pintype "passive"))
      (node (ref "U1") (pin "28") (pinfunction "PB2_28") (pintype "bidirectional"))
    )
    (net (code "28") (name "M2_1") (class "Default")
      (node (ref "R2") (pin "1") (pinfunction "1_1") (pintype "passive"))
      (node (ref "U1") (pin "27") (pinfunction "PB1_27") (pintype "bidirectional"))
    )
    (net (code "29") (name "M2_2") (class "Default")
      (node (ref "R3") (pin "1") (pinfunction "1_1") (pintype "passive"))
      (node (ref "U1") (pin "25") (pinfunction "PC5_25") (pintype "bidirectional"))
    )
    (net (code "30") (name "M2_3") (class "Default")
      (node (ref "R4") (pin "1") (pinfunction "1_1") (pintype "passive"))
      (node (ref "U1") (pin "23") (pinfunction "PA7_23") (pintype "bidirectional"))
    )
    (net (code "31") (name "M2_4") (class "Default")
      (node (ref "R5") (pin "1") (pinfunction "1_1") (pintype "passive"))
      (node (ref "U1") (pin "22") (pinfunction "PA6_22") (pintype "bidirectional"))
    )
    (net (code "32") (name "M2_5") (class "Default")
      (node (ref "R6") (pin "1") (pinfunction "1_1") (pintype "passive"))
      (node (ref "U1") (pin "21") (pinfunction "PA5_21") (pintype "bidirectional"))
    )
    (net (code "33") (name "M2_6") (class "Default")
      (node (ref "R7") (pin "1") (pinfunction "1_1") (pintype "passive"))
      (node (ref "U1") (pin "20") (pinfunction "PA4_20") (pintype "bidirectional"))
    )
    (net (code "34") (name "M2_7") (class "Default")
      (node (ref "R8") (pin "1") (pinfunction "1_1") (pintype "passive"))
      (node (ref "U1") (pin "29") (pinfunction "PB10_29") (pintype "bidirectional"))
    )
    (net (code "35") (name "M2_8") (class "Default")
      (node (ref "R9") (pin "1") (pinfunction "1_1") (pintype "passive"))
      (node (ref "U1") (pin "24") (pinfunction "PC4_24") (pintype "bidirectional"))
    )
    (net (code "36") (name "M2_9") (class "Default")
      (node (ref "R10") (pin "1") (pinfunction "1_1") (pintype "passive"))
      (node (ref "U1") (pin "26") (pinfunction "PB0_26") (pintype "bidirectional"))
    )
    (net (code "37") (name "NRST") (class "Default")
      (node (ref "JP1") (pin "5") (pinfunction "5_5") (pintype "passive"))
      (node (ref "U1") (pin "7") (pinfunction "NRST_7") (pintype "bidirectional"))
    )
    (net (code "38") (name "Net-(BAT1-+)") (class "Default")
      (node (ref "BAT1") (pin "1") (pinfunction "+_1") (pintype "power_in"))
      (node (ref "U1") (pin "1") (pinfunction "VBAT_1") (pintype "power_in"))
    )
    (net (code "39") (name "Net-(C10-Pad1)") (class "Default")
      (node (ref "C10") (pin "1") (pinfunction "1_1") (pintype "passive"))
      (node (ref "R38") (pin "1") (pinfunction "1_1") (pintype "passive"))
    )
    (net (code "40") (name "Net-(D1-PadA)") (class "Default")
      (node (ref "D1") (pin "A") (pinfunction "A_A") (pintype "passive"))
      (node (ref "L1") (pin "2") (pinfunction "2_2") (pintype "passive"))
      (node (ref "Q2") (pin "D") (pinfunction "D_D") (pintype "passive"))
      (node (ref "R38") (pin "2") (pinfunction "2_2") (pintype "passive"))
    )
    (net (code "41") (name "Net-(N1-PadA)") (class "Default")
      (node (ref "N1") (pin "A") (pinfunction "A_A") (pintype "bidirectional"))
      (node (ref "R34") (pin "1") (pinfunction "1_1") (pintype "passive"))
    )
    (net (code "42") (name "Net-(N2-PadA)") (class "Default")
      (node (ref "N2") (pin "A") (pinfunction "A_A") (pintype "bidirectional"))
      (node (ref "R33") (pin "1") (pinfunction "1_1") (pintype "passive"))
    )
    (net (code "43") (name "Net-(N3-PadA)") (class "Default")
      (node (ref "N3") (pin "A") (pinfunction "A_A") (pintype "bidirectional"))
      (node (ref "R32") (pin "1") (pinfunction "1_1") (pintype "passive"))
    )
    (net (code "44") (name "Net-(N4-PadA)") (class "Default")
      (node (ref "N4") (pin "A") (pinfunction "A_A") (pintype "bidirectional"))
      (node (ref "R31") (pin "1") (pinfunction "1_1") (pintype "passive"))
    )
    (net (code "45") (name "Net-(Q1-2)") (class "Default")
      (node (ref "C1") (pin "1") (pinfunction "1_1") (pintype "passive"))
      (node (ref "Q1") (pin "4") (pinfunction "2_4") (pintype "passive"))
      (node (ref "U1") (pin "3") (pinfunction "PC14-OSC32_IN_3") (pintype "bidirectional"))
    )
    (net (code "46") (name "Net-(R35-CCW)") (class "Default")
      (node (ref "R35") (pin "1") (pinfunction "CCW_1") (pintype "passive"))
      (node (ref "R40") (pin "2") (pinfunction "2_2") (pintype "passive"))
    )
    (net (code "47") (name "Net-(R35-CW)") (class "Default")
      (node (ref "R35") (pin "3") (pinfunction "CW_3") (pintype "passive"))
      (node (ref "R39") (pin "1") (pinfunction "1_1") (pintype "passive"))
    )
    (net (code "48") (name "Net-(R35-WIPER)") (class "Default")
      (node (ref "R35") (pin "2") (pinfunction "WIPER_2") (pintype "passive"))
      (node (ref "U32") (pin "1") (pinfunction "B_1") (pintype "power_in"))
    )
    (net (code "49") (name "Net-(U1-BOOT0)") (class "Default")
      (node (ref "R1") (pin "2") (pinfunction "2_2") (pintype "passive"))
      (node (ref "U1") (pin "60") (pinfunction "BOOT0_60") (pintype "input"))
    )
    (net (code "50") (name "Net-(U1-PC15-OSC32_OUT)") (class "Default")
      (node (ref "C2") (pin "2") (pinfunction "2_2") (pintype "passive"))
      (node (ref "Q1") (pin "1") (pinfunction "1_1") (pintype "passive"))
      (node (ref "U1") (pin "4") (pinfunction "PC15-OSC32_OUT_4") (pintype "bidirectional"))
    )
    (net (code "51") (name "Net-(U2-CONT)") (class "Default")
      (node (ref "U2") (pin "5") (pinfunction "CONT_5") (pintype "passive"))
      (node (ref "U32") (pin "3") (pinfunction "C_3") (pintype "output"))
    )
    (net (code "52") (name "Net-(U2-DISCH)") (class "Default")
      (node (ref "R36") (pin "1") (pinfunction "1_1") (pintype "passive"))
      (node (ref "R37") (pin "2") (pinfunction "2_2") (pintype "passive"))
      (node (ref "U2") (pin "7") (pinfunction "DISCH_7") (pintype "passive"))
    )
    (net (code "53") (name "Net-(U2-OUT)") (class "Default")
      (node (ref "Q2") (pin "G") (pinfunction "G_G") (pintype "passive"))
      (node (ref "U2") (pin "3") (pinfunction "OUT_3") (pintype "output"))
    )
    (net (code "54") (name "Net-(U2-THRES)") (class "Default")
      (node (ref "C12") (pin "1") (pinfunction "1_1") (pintype "passive"))
      (node (ref "R37") (pin "1") (pinfunction "1_1") (pintype "passive"))
      (node (ref "U2") (pin "2") (pinfunction "TRIG_2") (pintype "input"))
      (node (ref "U2") (pin "6") (pinfunction "THRES_6") (pintype "input"))
    )
    (net (code "55") (name "Net-(U3-B)") (class "Default")
      (node (ref "R28") (pin "2") (pinfunction "2_2") (pintype "passive"))
      (node (ref "U3") (pin "1") (pinfunction "B_1") (pintype "power_in"))
    )
    (net (code "56") (name "Net-(U3-C)") (class "Default")
      (node (ref "N1") (pin "0") (pinfunction "0_0") (pintype "bidirectional"))
      (node (ref "U3") (pin "3") (pinfunction "C_3") (pintype "output"))
    )
    (net (code "57") (name "Net-(U4-B)") (class "Default")
      (node (ref "R30") (pin "2") (pinfunction "2_2") (pintype "passive"))
      (node (ref "U4") (pin "1") (pinfunction "B_1") (pintype "power_in"))
    )
    (net (code "58") (name "Net-(U4-C)") (class "Default")
      (node (ref "N1") (pin "1") (pinfunction "1_1") (pintype "bidirectional"))
      (node (ref "U4") (pin "3") (pinfunction "C_3") (pintype "output"))
    )
    (net (code "59") (name "Net-(U5-B)") (class "Default")
      (node (ref "R27") (pin "2") (pinfunction "2_2") (pintype "passive"))
      (node (ref "U5") (pin "1") (pinfunction "B_1") (pintype "power_in"))
    )
    (net (code "60") (name "Net-(U5-C)") (class "Default")
      (node (ref "N2") (pin "0") (pinfunction "0_0") (pintype "bidirectional"))
      (node (ref "U5") (pin "3") (pinfunction "C_3") (pintype "output"))
    )
    (net (code "61") (name "Net-(U6-B)") (class "Default")
      (node (ref "R26") (pin "2") (pinfunction "2_2") (pintype "passive"))
      (node (ref "U6") (pin "1") (pinfunction "B_1") (pintype "power_in"))
    )
    (net (code "62") (name "Net-(U6-C)") (class "Default")
      (node (ref "N2") (pin "9") (pinfunction "9_9") (pintype "bidirectional"))
      (node (ref "U6") (pin "3") (pinfunction "C_3") (pintype "output"))
    )
    (net (code "63") (name "Net-(U7-B)") (class "Default")
      (node (ref "R25") (pin "2") (pinfunction "2_2") (pintype "passive"))
      (node (ref "U7") (pin "1") (pinfunction "B_1") (pintype "power_in"))
    )
    (net (code "64") (name "Net-(U7-C)") (class "Default")
      (node (ref "N2") (pin "8") (pinfunction "8_8") (pintype "bidirectional"))
      (node (ref "U7") (pin "3") (pinfunction "C_3") (pintype "output"))
    )
    (net (code "65") (name "Net-(U8-B)") (class "Default")
      (node (ref "R24") (pin "2") (pinfunction "2_2") (pintype "passive"))
      (node (ref "U8") (pin "1") (pinfunction "B_1") (pintype "power_in"))
    )
    (net (code "66") (name "Net-(U8-C)") (class "Default")
      (node (ref "N2") (pin "7") (pinfunction "7_7") (pintype "bidirectional"))
      (node (ref "U8") (pin "3") (pinfunction "C_3") (pintype "output"))
    )
    (net (code "67") (name "Net-(U9-B)") (class "Default")
      (node (ref "R23") (pin "2") (pinfunction "2_2") (pintype "passive"))
      (node (ref "U9") (pin "1") (pinfunction "B_1") (pintype "power_in"))
    )
    (net (code "68") (name "Net-(U9-C)") (class "Default")
      (node (ref "N2") (pin "6") (pinfunction "6_6") (pintype "bidirectional"))
      (node (ref "U9") (pin "3") (pinfunction "C_3") (pintype "output"))
    )
    (net (code "69") (name "Net-(U10-B)") (class "Default")
      (node (ref "R22") (pin "2") (pinfunction "2_2") (pintype "passive"))
      (node (ref "U10") (pin "1") (pinfunction "B_1") (pintype "power_in"))
    )
    (net (code "70") (name "Net-(U10-C)") (class "Default")
      (node (ref "N2") (pin "5") (pinfunction "5_5") (pintype "bidirectional"))
      (node (ref "U10") (pin "3") (pinfunction "C_3") (pintype "output"))
    )
    (net (code "71") (name "Net-(U11-B)") (class "Default")
      (node (ref "R21") (pin "2") (pinfunction "2_2") (pintype "passive"))
      (node (ref "U11") (pin "1") (pinfunction "B_1") (pintype "power_in"))
    )
    (net (code "72") (name "Net-(U11-C)") (class "Default")
      (node (ref "N2") (pin "4") (pinfunction "4_4") (pintype "bidirectional"))
      (node (ref "U11") (pin "3") (pinfunction "C_3") (pintype "output"))
    )
    (net (code "73") (name "Net-(U12-B)") (class "Default")
      (node (ref "R20") (pin "2") (pinfunction "2_2") (pintype "passive"))
      (node (ref "U12") (pin "1") (pinfunction "B_1") (pintype "power_in"))
    )
    (net (code "74") (name "Net-(U12-C)") (class "Default")
      (node (ref "N2") (pin "3") (pinfunction "3_3") (pintype "bidirectional"))
      (node (ref "U12") (pin "3") (pinfunction "C_3") (pintype "output"))
    )
    (net (code "75") (name "Net-(U13-B)") (class "Default")
      (node (ref "R19") (pin "2") (pinfunction "2_2") (pintype "passive"))
      (node (ref "U13") (pin "1") (pinfunction "B_1") (pintype "power_in"))
    )
    (net (code "76") (name "Net-(U13-C)") (class "Default")
      (node (ref "N2") (pin "2") (pinfunction "2_2") (pintype "bidirectional"))
      (node (ref "U13") (pin "3") (pinfunction "C_3") (pintype "output"))
    )
    (net (code "77") (name "Net-(U14-B)") (class "Default")
      (node (ref "R18") (pin "2") (pinfunction "2_2") (pintype "passive"))
      (node (ref "U14") (pin "1") (pinfunction "B_1") (pintype "power_in"))
    )
    (net (code "78") (name "Net-(U14-C)") (class "Default")
      (node (ref "N2") (pin "1") (pinfunction "1_1") (pintype "bidirectional"))
      (node (ref "U14") (pin "3") (pinfunction "C_3") (pintype "output"))
    )
    (net (code "79") (name "Net-(U15-B)") (class "Default")
      (node (ref "R12") (pin "2") (pinfunction "2_2") (pintype "passive"))
      (node (ref "U15") (pin "1") (pinfunction "B_1") (pintype "power_in"))
    )
    (net (code "80") (name "Net-(U15-C)") (class "Default")
      (node (ref "N3") (pin "0") (pinfunction "0_0") (pintype "bidirectional"))
      (node (ref "U15") (pin "3") (pinfunction "C_3") (pintype "output"))
    )
    (net (code "81") (name "Net-(U16-B)") (class "Default")
      (node (ref "R13") (pin "2") (pinfunction "2_2") (pintype "passive"))
      (node (ref "U16") (pin "1") (pinfunction "B_1") (pintype "power_in"))
    )
    (net (code "82") (name "Net-(U16-C)") (class "Default")
      (node (ref "N3") (pin "5") (pinfunction "5_5") (pintype "bidirectional"))
      (node (ref "U16") (pin "3") (pinfunction "C_3") (pintype "output"))
    )
    (net (code "83") (name "Net-(U17-B)") (class "Default")
      (node (ref "R14") (pin "2") (pinfunction "2_2") (pintype "passive"))
      (node (ref "U17") (pin "1") (pinfunction "B_1") (pintype "power_in"))
    )
    (net (code "84") (name "Net-(U17-C)") (class "Default")
      (node (ref "N3") (pin "4") (pinfunction "4_4") (pintype "bidirectional"))
      (node (ref "U17") (pin "3") (pinfunction "C_3") (pintype "output"))
    )
    (net (code "85") (name "Net-(U18-B)") (class "Default")
      (node (ref "R15") (pin "2") (pinfunction "2_2") (pintype "passive"))
      (node (ref "U18") (pin "1") (pinfunction "B_1") (pintype "power_in"))
    )
    (net (code "86") (name "Net-(U18-C)") (class "Default")
      (node (ref "N3") (pin "3") (pinfunction "3_3") (pintype "bidirectional"))
      (node (ref "U18") (pin "3") (pinfunction "C_3") (pintype "output"))
    )
    (net (code "87") (name "Net-(U19-B)") (class "Default")
      (node (ref "R16") (pin "2") (pinfunction "2_2") (pintype "passive"))
      (node (ref "U19") (pin "1") (pinfunction "B_1") (pintype "power_in"))
    )
    (net (code "88") (name "Net-(U19-C)") (class "Default")
      (node (ref "N3") (pin "2") (pinfunction "2_2") (pintype "bidirectional"))
      (node (ref "U19") (pin "3") (pinfunction "C_3") (pintype "output"))
    )
    (net (code "89") (name "Net-(U20-B)") (class "Default")
      (node (ref "R17") (pin "2") (pinfunction "2_2") (pintype "passive"))
      (node (ref "U20") (pin "1") (pinfunction "B_1") (pintype "power_in"))
    )
    (net (code "90") (name "Net-(U20-C)") (class "Default")
      (node (ref "N3") (pin "1") (pinfunction "1_1") (pintype "bidirectional"))
      (node (ref "U20") (pin "3") (pinfunction "C_3") (pintype "output"))
    )
    (net (code "91") (name "Net-(U21-B)") (class "Default")
      (node (ref "R11") (pin "2") (pinfunction "2_2") (pintype "passive"))
      (node (ref "U21") (pin "1") (pinfunction "B_1") (pintype "power_in"))
    )
    (net (code "92") (name "Net-(U21-C)") (class "Default")
      (node (ref "N4") (pin "0") (pinfunction "0_0") (pintype "bidirectional"))
      (node (ref "U21") (pin "3") (pinfunction "C_3") (pintype "output"))
    )
    (net (code "93") (name "Net-(U22-B)") (class "Default")
      (node (ref "R10") (pin "2") (pinfunction "2_2") (pintype "passive"))
      (node (ref "U22") (pin "1") (pinfunction "B_1") (pintype "power_in"))
    )
    (net (code "94") (name "Net-(U22-C)") (class "Default")
      (node (ref "N4") (pin "9") (pinfunction "9_9") (pintype "bidirectional"))
      (node (ref "U22") (pin "3") (pinfunction "C_3") (pintype "output"))
    )
    (net (code "95") (name "Net-(U23-B)") (class "Default")
      (node (ref "R9") (pin "2") (pinfunction "2_2") (pintype "passive"))
      (node (ref "U23") (pin "1") (pinfunction "B_1") (pintype "power_in"))
    )
    (net (code "96") (name "Net-(U23-C)") (class "Default")
      (node (ref "N4") (pin "8") (pinfunction "8_8") (pintype "bidirectional"))
      (node (ref "U23") (pin "3") (pinfunction "C_3") (pintype "output"))
    )
    (net (code "97") (name "Net-(U24-B)") (class "Default")
      (node (ref "R8") (pin "2") (pinfunction "2_2") (pintype "passive"))
      (node (ref "U24") (pin "1") (pinfunction "B_1") (pintype "power_in"))
    )
    (net (code "98") (name "Net-(U24-C)") (class "Default")
      (node (ref "N4") (pin "7") (pinfunction "7_7") (pintype "bidirectional"))
      (node (ref "U24") (pin "3") (pinfunction "C_3") (pintype "output"))
    )
    (net (code "99") (name "Net-(U25-B)") (class "Default")
      (node (ref "R7") (pin "2") (pinfunction "2_2") (pintype "passive"))
      (node (ref "U25") (pin "1") (pinfunction "B_1") (pintype "power_in"))
    )
    (net (code "100") (name "Net-(U25-C)") (class "Default")
      (node (ref "N4") (pin "6") (pinfunction "6_6") (pintype "bidirectional"))
      (node (ref "U25") (pin "3") (pinfunction "C_3") (pintype "output"))
    )
    (net (code "101") (name "Net-(U26-B)") (class "Default")
      (node (ref "R6") (pin "2") (pinfunction "2_2") (pintype "passive"))
      (node (ref "U26") (pin "1") (pinfunction "B_1") (pintype "power_in"))
    )
    (net (code "102") (name "Net-(U26-C)") (class "Default")
      (node (ref "N4") (pin "5") (pinfunction "5_5") (pintype "bidirectional"))
      (node (ref "U26") (pin "3") (pinfunction "C_3") (pintype "output"))
    )
    (net (code "103") (name "Net-(U27-B)") (class "Default")
      (node (ref "R5") (pin "2") (pinfunction "2_2") (pintype "passive"))
      (node (ref "U27") (pin "1") (pinfunction "B_1") (pintype "power_in"))
    )
    (net (code "104") (name "Net-(U27-C)") (class "Default")
      (node (ref "N4") (pin "4") (pinfunction "4_4") (pintype "bidirectional"))
      (node (ref "U27") (pin "3") (pinfunction "C_3") (pintype "output"))
    )
    (net (code "105") (name "Net-(U28-B)") (class "Default")
      (node (ref "R4") (pin "2") (pinfunction "2_2") (pintype "passive"))
      (node (ref "U28") (pin "1") (pinfunction "B_1") (pintype "power_in"))
    )
    (net (code "106") (name "Net-(U28-C)") (class "Default")
      (node (ref "N4") (pin "3") (pinfunction "3_3") (pintype "bidirectional"))
      (node (ref "U28") (pin "3") (pinfunction "C_3") (pintype "output"))
    )
    (net (code "107") (name "Net-(U29-B)") (class "Default")
      (node (ref "R3") (pin "2") (pinfunction "2_2") (pintype "passive"))
      (node (ref "U29") (pin "1") (pinfunction "B_1") (pintype "power_in"))
    )
    (net (code "108") (name "Net-(U29-C)") (class "Default")
      (node (ref "N4") (pin "2") (pinfunction "2_2") (pintype "bidirectional"))
      (node (ref "U29") (pin "3") (pinfunction "C_3") (pintype "output"))
    )
    (net (code "109") (name "Net-(U30-B)") (class "Default")
      (node (ref "R2") (pin "2") (pinfunction "2_2") (pintype "passive"))
      (node (ref "U30") (pin "1") (pinfunction "B_1") (pintype "power_in"))
    )
    (net (code "110") (name "Net-(U30-C)") (class "Default")
      (node (ref "N4") (pin "1") (pinfunction "1_1") (pintype "bidirectional"))
      (node (ref "U30") (pin "3") (pinfunction "C_3") (pintype "output"))
    )
    (net (code "111") (name "Net-(U31-B)") (class "Default")
      (node (ref "R29") (pin "2") (pinfunction "2_2") (pintype "passive"))
      (node (ref "U31") (pin "1") (pinfunction "B_1") (pintype "power_in"))
    )
    (net (code "112") (name "Net-(U31-C)") (class "Default")
      (node (ref "N1") (pin "2") (pinfunction "2_2") (pintype "bidirectional"))
      (node (ref "U31") (pin "3") (pinfunction "C_3") (pintype "output"))
    )
    (net (code "113") (name "SWCLK") (class "Default")
      (node (ref "JP1") (pin "2") (pinfunction "2_2") (pintype "passive"))
      (node (ref "U1") (pin "49") (pinfunction "PA14(SWCLK)_49") (pintype "bidirectional"))
    )
    (net (code "114") (name "SWDIO") (class "Default")
      (node (ref "JP1") (pin "4") (pinfunction "4_4") (pintype "passive"))
      (node (ref "U1") (pin "46") (pinfunction "PA13(SWDAT)_46") (pintype "bidirectional"))
    )
    (net (code "115") (name "TEMP") (class "Default")
      (node (ref "JP3") (pin "2") (pinfunction "2_2") (pintype "passive"))
      (node (ref "U1") (pin "33") (pinfunction "PB12_33") (pintype "bidirectional"))
    )
    (net (code "116") (name "unconnected-(N1-Pad3)") (class "Default")
      (node (ref "N1") (pin "3") (pinfunction "3_3") (pintype "bidirectional"))
    )
    (net (code "117") (name "unconnected-(N1-Pad4)") (class "Default")
      (node (ref "N1") (pin "4") (pinfunction "4_4") (pintype "bidirectional"))
    )
    (net (code "118") (name "unconnected-(N1-Pad5)") (class "Default")
      (node (ref "N1") (pin "5") (pinfunction "5_5") (pintype "bidirectional"))
    )
    (net (code "119") (name "unconnected-(N1-Pad6)") (class "Default")
      (node (ref "N1") (pin "6") (pinfunction "6_6") (pintype "bidirectional"))
    )
    (net (code "120") (name "unconnected-(N1-Pad7)") (class "Default")
      (node (ref "N1") (pin "7") (pinfunction "7_7") (pintype "bidirectional"))
    )
    (net (code "121") (name "unconnected-(N1-Pad8)") (class "Default")
      (node (ref "N1") (pin "8") (pinfunction "8_8") (pintype "bidirectional"))
    )
    (net (code "122") (name "unconnected-(N1-Pad9)") (class "Default")
      (node (ref "N1") (pin "9") (pinfunction "9_9") (pintype "bidirectional"))
    )
    (net (code "123") (name "unconnected-(N3-Pad6)") (class "Default")
      (node (ref "N3") (pin "6") (pinfunction "6_6") (pintype "bidirectional"))
    )
    (net (code "124") (name "unconnected-(N3-Pad7)") (class "Default")
      (node (ref "N3") (pin "7") (pinfunction "7_7") (pintype "bidirectional"))
    )
    (net (code "125") (name "unconnected-(N3-Pad8)") (class "Default")
      (node (ref "N3") (pin "8") (pinfunction "8_8") (pintype "bidirectional"))
    )
    (net (code "126") (name "unconnected-(N3-Pad9)") (class "Default")
      (node (ref "N3") (pin "9") (pinfunction "9_9") (pintype "bidirectional"))
    )
    (net (code "127") (name "unconnected-(S1-Pad4)") (class "Default")
      (node (ref "S1") (pin "4") (pinfunction "4_4") (pintype "passive"))
    )
    (net (code "128") (name "unconnected-(S2-Pad4)") (class "Default")
      (node (ref "S2") (pin "4") (pinfunction "4_4") (pintype "passive"))
    )
    (net (code "129") (name "unconnected-(S3-Pad4)") (class "Default")
      (node (ref "S3") (pin "4") (pinfunction "4_4") (pintype "passive"))
    )
    (net (code "130") (name "unconnected-(U1-PA0-Pad14)") (class "Default")
      (node (ref "U1") (pin "14") (pinfunction "PA0_14") (pintype "bidirectional"))
    )
    (net (code "131") (name "unconnected-(U1-PA1-Pad15)") (class "Default")
      (node (ref "U1") (pin "15") (pinfunction "PA1_15") (pintype "bidirectional"))
    )
    (net (code "132") (name "unconnected-(U1-PA2-Pad16)") (class "Default")
      (node (ref "U1") (pin "16") (pinfunction "PA2_16") (pintype "bidirectional"))
    )
    (net (code "133") (name "unconnected-(U1-PB8-Pad61)") (class "Default")
      (node (ref "U1") (pin "61") (pinfunction "PB8_61") (pintype "bidirectional"))
    )
    (net (code "134") (name "unconnected-(U1-PB9-Pad62)") (class "Default")
      (node (ref "U1") (pin "62") (pinfunction "PB9_62") (pintype "bidirectional"))
    )
    (net (code "135") (name "unconnected-(U1-PB11-Pad30)") (class "Default")
      (node (ref "U1") (pin "30") (pinfunction "PB11_30") (pintype "bidirectional"))
    )
    (net (code "136") (name "unconnected-(U1-PC0-Pad8)") (class "Default")
      (node (ref "U1") (pin "8") (pinfunction "PC0_8") (pintype "bidirectional"))
    )
    (net (code "137") (name "unconnected-(U1-PC1-Pad9)") (class "Default")
      (node (ref "U1") (pin "9") (pinfunction "PC1_9") (pintype "bidirectional"))
    )
    (net (code "138") (name "unconnected-(U1-PC2-Pad10)") (class "Default")
      (node (ref "U1") (pin "10") (pinfunction "PC2_10") (pintype "bidirectional"))
    )
    (net (code "139") (name "unconnected-(U1-PC3-Pad11)") (class "Default")
      (node (ref "U1") (pin "11") (pinfunction "PC3_11") (pintype "bidirectional"))
    )
    (net (code "140") (name "unconnected-(U1-PC6-Pad37)") (class "Default")
      (node (ref "U1") (pin "37") (pinfunction "PC6_37") (pintype "bidirectional"))
    )
    (net (code "141") (name "unconnected-(U1-PC7-Pad38)") (class "Default")
      (node (ref "U1") (pin "38") (pinfunction "PC7_38") (pintype "bidirectional"))
    )
    (net (code "142") (name "unconnected-(U1-PC13-Pad2)") (class "Default")
      (node (ref "U1") (pin "2") (pinfunction "PC13_2") (pintype "bidirectional"))
    )
    (net (code "143") (name "unconnected-(U1-PD7-Pad59)") (class "Default")
      (node (ref "U1") (pin "59") (pinfunction "PD7_59") (pintype "bidirectional"))
    )
    (net (code "144") (name "unconnected-(U1-PF0-OSC_IN-Pad5)") (class "Default")
      (node (ref "U1") (pin "5") (pinfunction "PF0-OSC_IN_5") (pintype "bidirectional"))
    )
    (net (code "145") (name "unconnected-(U1-PF1-OSC_OUT-Pad6)") (class "Default")
      (node (ref "U1") (pin "6") (pinfunction "PF1-OSC_OUT_6") (pintype "bidirectional"))
    )
    (net (code "146") (name "unconnected-(U1-PF6-Pad47)") (class "Default")
      (node (ref "U1") (pin "47") (pinfunction "PF6_47") (pintype "bidirectional"))
    )
    (net (code "147") (name "unconnected-(U1-PF7-Pad48)") (class "Default")
      (node (ref "U1") (pin "48") (pinfunction "PF7_48") (pintype "bidirectional"))
    )
  )
)
